# Minna_IO.net
KiCad netlist of a schematic drawn in Altium Designer
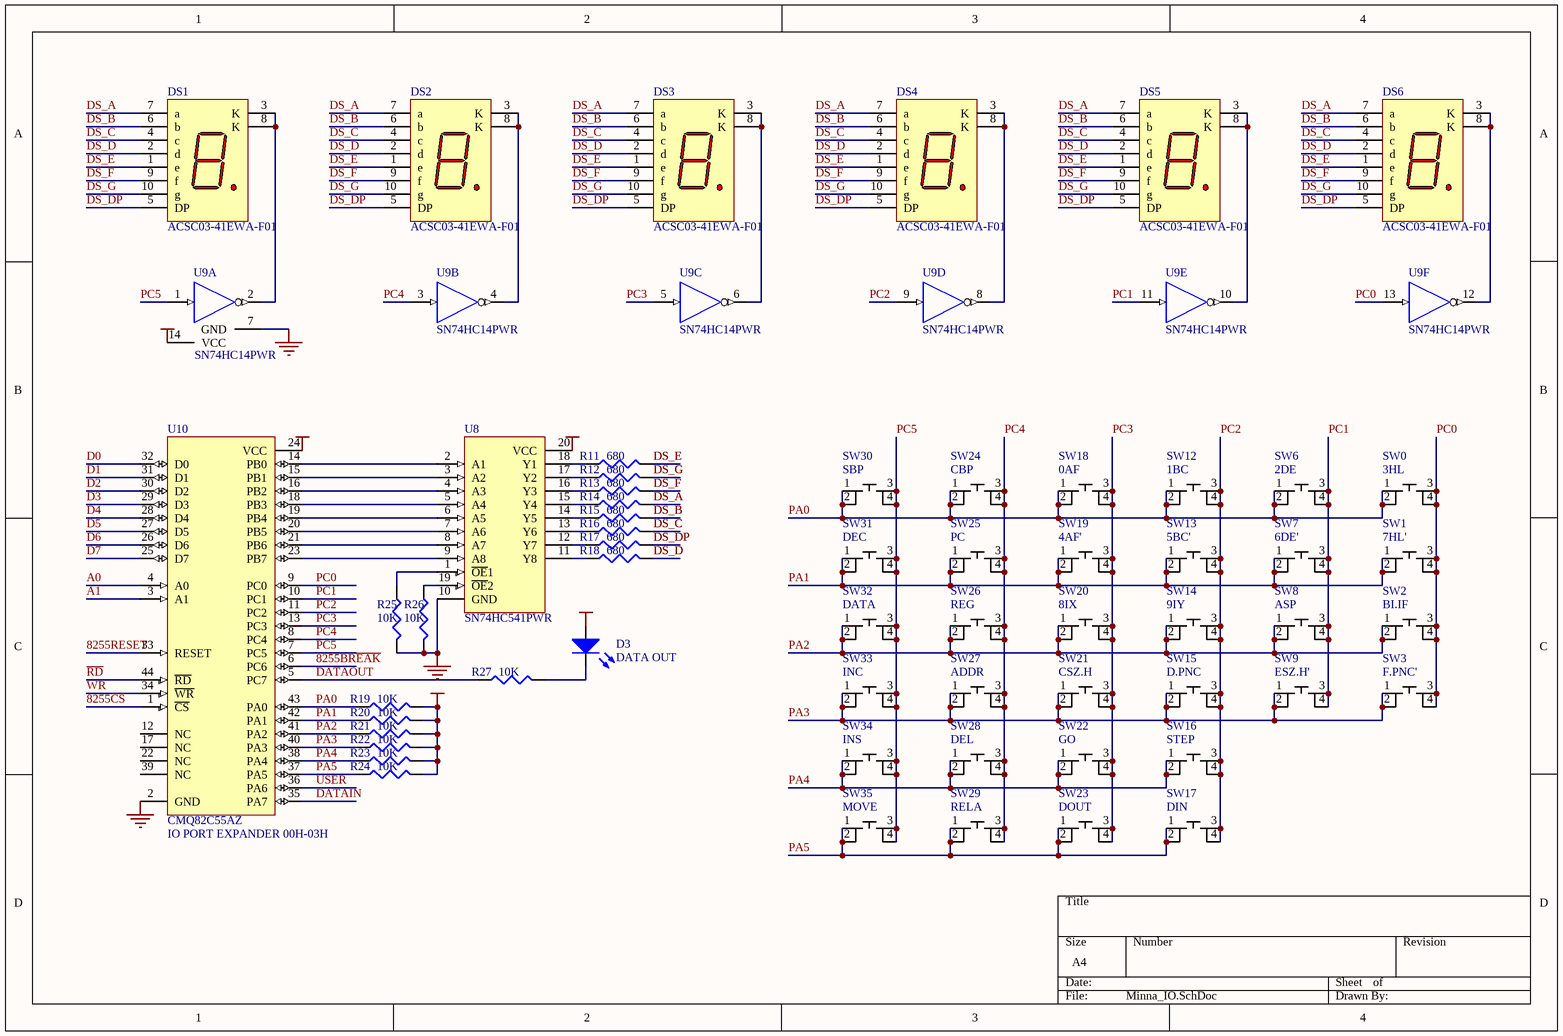
[diagram p0: Minna_IO.SchDoc]

(export (version "E")
  (design (tool "Eeschema 10.0.6"))
  (components
    (comp (ref "D3")
      (value "DATA OUT")
      (footprint "Minna Project:APG1608")
      (description "LED 1.6X0.8MM 571NM GRN CLR SMD")
      (libsource (lib "Minna Project") (part "APG1608CGKC/T"))
    )
    (comp (ref "DS1")
      (value "ACSC03-41EWA-F01")
      (footprint "Minna Project:ACSC03-41EWA-F01")
      (description "DISPLAY 0.3\" 627NM SGL RED SMD")
      (libsource (lib "Minna Project") (part "ACSC03-41EWA-F01"))
    )
    (comp (ref "DS2")
      (value "ACSC03-41EWA-F01")
      (footprint "Minna Project:ACSC03-41EWA-F01")
      (description "DISPLAY 0.3\" 627NM SGL RED SMD")
      (libsource (lib "Minna Project") (part "ACSC03-41EWA-F01"))
    )
    (comp (ref "DS3")
      (value "ACSC03-41EWA-F01")
      (footprint "Minna Project:ACSC03-41EWA-F01")
      (description "DISPLAY 0.3\" 627NM SGL RED SMD")
      (libsource (lib "Minna Project") (part "ACSC03-41EWA-F01"))
    )
    (comp (ref "DS4")
      (value "ACSC03-41EWA-F01")
      (footprint "Minna Project:ACSC03-41EWA-F01")
      (description "DISPLAY 0.3\" 627NM SGL RED SMD")
      (libsource (lib "Minna Project") (part "ACSC03-41EWA-F01"))
    )
    (comp (ref "DS5")
      (value "ACSC03-41EWA-F01")
      (footprint "Minna Project:ACSC03-41EWA-F01")
      (description "DISPLAY 0.3\" 627NM SGL RED SMD")
      (libsource (lib "Minna Project") (part "ACSC03-41EWA-F01"))
    )
    (comp (ref "DS6")
      (value "ACSC03-41EWA-F01")
      (footprint "Minna Project:ACSC03-41EWA-F01")
      (description "DISPLAY 0.3\" 627NM SGL RED SMD")
      (libsource (lib "Minna Project") (part "ACSC03-41EWA-F01"))
    )
    (comp (ref "R11")
      (value "680")
      (footprint "Minna Project:0603")
      (description "RES 680 OHM 1/10W 1% 0603 SMD")
      (libsource (lib "Minna Project") (part "MCR03EZPFX"))
    )
    (comp (ref "R12")
      (value "680")
      (footprint "Minna Project:0603")
      (description "RES 680 OHM 1/10W 1% 0603 SMD")
      (libsource (lib "Minna Project") (part "MCR03EZPFX"))
    )
    (comp (ref "R13")
      (value "680")
      (footprint "Minna Project:0603")
      (description "RES 680 OHM 1/10W 1% 0603 SMD")
      (libsource (lib "Minna Project") (part "MCR03EZPFX"))
    )
    (comp (ref "R14")
      (value "680")
      (footprint "Minna Project:0603")
      (description "RES 680 OHM 1/10W 1% 0603 SMD")
      (libsource (lib "Minna Project") (part "MCR03EZPFX"))
    )
    (comp (ref "R15")
      (value "680")
      (footprint "Minna Project:0603")
      (description "RES 680 OHM 1/10W 1% 0603 SMD")
      (libsource (lib "Minna Project") (part "MCR03EZPFX"))
    )
    (comp (ref "R16")
      (value "680")
      (footprint "Minna Project:0603")
      (description "RES 680 OHM 1/10W 1% 0603 SMD")
      (libsource (lib "Minna Project") (part "MCR03EZPFX"))
    )
    (comp (ref "R17")
      (value "680")
      (footprint "Minna Project:0603")
      (description "RES 680 OHM 1/10W 1% 0603 SMD")
      (libsource (lib "Minna Project") (part "MCR03EZPFX"))
    )
    (comp (ref "R18")
      (value "680")
      (footprint "Minna Project:0603")
      (description "RES 680 OHM 1/10W 1% 0603 SMD")
      (libsource (lib "Minna Project") (part "MCR03EZPFX"))
    )
    (comp (ref "R19")
      (value "10K")
      (footprint "Minna Project:0603")
      (description "RES 10.0K OHM 1/10W 1% 0603 SMD")
      (libsource (lib "Minna Project") (part "MCR03EZPFX"))
    )
    (comp (ref "R20")
      (value "10K")
      (footprint "Minna Project:0603")
      (description "RES 10.0K OHM 1/10W 1% 0603 SMD")
      (libsource (lib "Minna Project") (part "MCR03EZPFX"))
    )
    (comp (ref "R21")
      (value "10K")
      (footprint "Minna Project:0603")
      (description "RES 10.0K OHM 1/10W 1% 0603 SMD")
      (libsource (lib "Minna Project") (part "MCR03EZPFX"))
    )
    (comp (ref "R22")
      (value "10K")
      (footprint "Minna Project:0603")
      (description "RES 10.0K OHM 1/10W 1% 0603 SMD")
      (libsource (lib "Minna Project") (part "MCR03EZPFX"))
    )
    (comp (ref "R23")
      (value "10K")
      (footprint "Minna Project:0603")
      (description "RES 10.0K OHM 1/10W 1% 0603 SMD")
      (libsource (lib "Minna Project") (part "MCR03EZPFX"))
    )
    (comp (ref "R24")
      (value "10K")
      (footprint "Minna Project:0603")
      (description "RES 10.0K OHM 1/10W 1% 0603 SMD")
      (libsource (lib "Minna Project") (part "MCR03EZPFX"))
    )
    (comp (ref "R25")
      (value "10K")
      (footprint "Minna Project:0603")
      (description "RES 10.0K OHM 1/10W 1% 0603 SMD")
      (libsource (lib "Minna Project") (part "MCR03EZPFX"))
    )
    (comp (ref "R26")
      (value "10K")
      (footprint "Minna Project:0603")
      (description "RES 10.0K OHM 1/10W 1% 0603 SMD")
      (libsource (lib "Minna Project") (part "MCR03EZPFX"))
    )
    (comp (ref "R27")
      (value "10K")
      (footprint "Minna Project:0603")
      (description "RES 10.0K OHM 1/10W 1% 0603 SMD")
      (libsource (lib "Minna Project") (part "MCR03EZPFX"))
    )
    (comp (ref "SW0")
      (value "3HL")
      (footprint "Minna Project:PTS645SM43SMTR LFS")
      (description "SWITCH TACT 6MM 160GF H=4.3MM")
      (libsource (lib "Minna Project") (part "PTS645SM43SMTR LFS"))
    )
    (comp (ref "SW1")
      (value "7HL'")
      (footprint "Minna Project:PTS645SM43SMTR LFS")
      (description "SWITCH TACT 6MM 160GF H=4.3MM")
      (libsource (lib "Minna Project") (part "PTS645SM43SMTR LFS"))
    )
    (comp (ref "SW2")
      (value "BI.IF")
      (footprint "Minna Project:PTS645SM43SMTR LFS")
      (description "SWITCH TACT 6MM 160GF H=4.3MM")
      (libsource (lib "Minna Project") (part "PTS645SM43SMTR LFS"))
    )
    (comp (ref "SW3")
      (value "F.PNC'")
      (footprint "Minna Project:PTS645SM43SMTR LFS")
      (description "SWITCH TACT 6MM 160GF H=4.3MM")
      (libsource (lib "Minna Project") (part "PTS645SM43SMTR LFS"))
    )
    (comp (ref "SW6")
      (value "2DE")
      (footprint "Minna Project:PTS645SM43SMTR LFS")
      (description "SWITCH TACT 6MM 160GF H=4.3MM")
      (libsource (lib "Minna Project") (part "PTS645SM43SMTR LFS"))
    )
    (comp (ref "SW7")
      (value "6DE'")
      (footprint "Minna Project:PTS645SM43SMTR LFS")
      (description "SWITCH TACT 6MM 160GF H=4.3MM")
      (libsource (lib "Minna Project") (part "PTS645SM43SMTR LFS"))
    )
    (comp (ref "SW8")
      (value "ASP")
      (footprint "Minna Project:PTS645SM43SMTR LFS")
      (description "SWITCH TACT 6MM 160GF H=4.3MM")
      (libsource (lib "Minna Project") (part "PTS645SM43SMTR LFS"))
    )
    (comp (ref "SW9")
      (value "ESZ.H'")
      (footprint "Minna Project:PTS645SM43SMTR LFS")
      (description "SWITCH TACT 6MM 160GF H=4.3MM")
      (libsource (lib "Minna Project") (part "PTS645SM43SMTR LFS"))
    )
    (comp (ref "SW12")
      (value "1BC")
      (footprint "Minna Project:PTS645SM43SMTR LFS")
      (description "SWITCH TACT 6MM 160GF H=4.3MM")
      (libsource (lib "Minna Project") (part "PTS645SM43SMTR LFS"))
    )
    (comp (ref "SW13")
      (value "5BC'")
      (footprint "Minna Project:PTS645SM43SMTR LFS")
      (description "SWITCH TACT 6MM 160GF H=4.3MM")
      (libsource (lib "Minna Project") (part "PTS645SM43SMTR LFS"))
    )
    (comp (ref "SW14")
      (value "9IY")
      (footprint "Minna Project:PTS645SM43SMTR LFS")
      (description "SWITCH TACT 6MM 160GF H=4.3MM")
      (libsource (lib "Minna Project") (part "PTS645SM43SMTR LFS"))
    )
    (comp (ref "SW15")
      (value "D.PNC")
      (footprint "Minna Project:PTS645SM43SMTR LFS")
      (description "SWITCH TACT 6MM 160GF H=4.3MM")
      (libsource (lib "Minna Project") (part "PTS645SM43SMTR LFS"))
    )
    (comp (ref "SW16")
      (value "STEP")
      (footprint "Minna Project:PTS645SM43SMTR LFS")
      (description "SWITCH TACT 6MM 160GF H=4.3MM")
      (libsource (lib "Minna Project") (part "PTS645SM43SMTR LFS"))
    )
    (comp (ref "SW17")
      (value "DIN")
      (footprint "Minna Project:PTS645SM43SMTR LFS")
      (description "SWITCH TACT 6MM 160GF H=4.3MM")
      (libsource (lib "Minna Project") (part "PTS645SM43SMTR LFS"))
    )
    (comp (ref "SW18")
      (value "0AF")
      (footprint "Minna Project:PTS645SM43SMTR LFS")
      (description "SWITCH TACT 6MM 160GF H=4.3MM")
      (libsource (lib "Minna Project") (part "PTS645SM43SMTR LFS"))
    )
    (comp (ref "SW19")
      (value "4AF'")
      (footprint "Minna Project:PTS645SM43SMTR LFS")
      (description "SWITCH TACT 6MM 160GF H=4.3MM")
      (libsource (lib "Minna Project") (part "PTS645SM43SMTR LFS"))
    )
    (comp (ref "SW20")
      (value "8IX")
      (footprint "Minna Project:PTS645SM43SMTR LFS")
      (description "SWITCH TACT 6MM 160GF H=4.3MM")
      (libsource (lib "Minna Project") (part "PTS645SM43SMTR LFS"))
    )
    (comp (ref "SW21")
      (value "CSZ.H")
      (footprint "Minna Project:PTS645SM43SMTR LFS")
      (description "SWITCH TACT 6MM 160GF H=4.3MM")
      (libsource (lib "Minna Project") (part "PTS645SM43SMTR LFS"))
    )
    (comp (ref "SW22")
      (value "GO")
      (footprint "Minna Project:PTS645SM43SMTR LFS")
      (description "SWITCH TACT 6MM 160GF H=4.3MM")
      (libsource (lib "Minna Project") (part "PTS645SM43SMTR LFS"))
    )
    (comp (ref "SW23")
      (value "DOUT")
      (footprint "Minna Project:PTS645SM43SMTR LFS")
      (description "SWITCH TACT 6MM 160GF H=4.3MM")
      (libsource (lib "Minna Project") (part "PTS645SM43SMTR LFS"))
    )
    (comp (ref "SW24")
      (value "CBP")
      (footprint "Minna Project:PTS645SM43SMTR LFS")
      (description "SWITCH TACT 6MM 160GF H=4.3MM")
      (libsource (lib "Minna Project") (part "PTS645SM43SMTR LFS"))
    )
    (comp (ref "SW25")
      (value "PC")
      (footprint "Minna Project:PTS645SM43SMTR LFS")
      (description "SWITCH TACT 6MM 160GF H=4.3MM")
      (libsource (lib "Minna Project") (part "PTS645SM43SMTR LFS"))
    )
    (comp (ref "SW26")
      (value "REG")
      (footprint "Minna Project:PTS645SM43SMTR LFS")
      (description "SWITCH TACT 6MM 160GF H=4.3MM")
      (libsource (lib "Minna Project") (part "PTS645SM43SMTR LFS"))
    )
    (comp (ref "SW27")
      (value "ADDR")
      (footprint "Minna Project:PTS645SM43SMTR LFS")
      (description "SWITCH TACT 6MM 160GF H=4.3MM")
      (libsource (lib "Minna Project") (part "PTS645SM43SMTR LFS"))
    )
    (comp (ref "SW28")
      (value "DEL")
      (footprint "Minna Project:PTS645SM43SMTR LFS")
      (description "SWITCH TACT 6MM 160GF H=4.3MM")
      (libsource (lib "Minna Project") (part "PTS645SM43SMTR LFS"))
    )
    (comp (ref "SW29")
      (value "RELA")
      (footprint "Minna Project:PTS645SM43SMTR LFS")
      (description "SWITCH TACT 6MM 160GF H=4.3MM")
      (libsource (lib "Minna Project") (part "PTS645SM43SMTR LFS"))
    )
    (comp (ref "SW30")
      (value "SBP")
      (footprint "Minna Project:PTS645SM43SMTR LFS")
      (description "SWITCH TACT 6MM 160GF H=4.3MM")
      (libsource (lib "Minna Project") (part "PTS645SM43SMTR LFS"))
    )
    (comp (ref "SW31")
      (value "DEC")
      (footprint "Minna Project:PTS645SM43SMTR LFS")
      (description "SWITCH TACT 6MM 160GF H=4.3MM")
      (libsource (lib "Minna Project") (part "PTS645SM43SMTR LFS"))
    )
    (comp (ref "SW32")
      (value "DATA")
      (footprint "Minna Project:PTS645SM43SMTR LFS")
      (description "SWITCH TACT 6MM 160GF H=4.3MM")
      (libsource (lib "Minna Project") (part "PTS645SM43SMTR LFS"))
    )
    (comp (ref "SW33")
      (value "INC")
      (footprint "Minna Project:PTS645SM43SMTR LFS")
      (description "SWITCH TACT 6MM 160GF H=4.3MM")
      (libsource (lib "Minna Project") (part "PTS645SM43SMTR LFS"))
    )
    (comp (ref "SW34")
      (value "INS")
      (footprint "Minna Project:PTS645SM43SMTR LFS")
      (description "SWITCH TACT 6MM 160GF H=4.3MM")
      (libsource (lib "Minna Project") (part "PTS645SM43SMTR LFS"))
    )
    (comp (ref "SW35")
      (value "MOVE")
      (footprint "Minna Project:PTS645SM43SMTR LFS")
      (description "SWITCH TACT 6MM 160GF H=4.3MM")
      (libsource (lib "Minna Project") (part "PTS645SM43SMTR LFS"))
    )
    (comp (ref "U8")
      (value "SN74HC541PWR")
      (footprint "Minna Project:PW020")
      (description "IC BUFF/DVR TRI-ST 8BIT 20TSSOP")
      (libsource (lib "Minna Project") (part "SN74HC541PWR"))
    )
    (comp (ref "U9")
      (value "SN74HC14PWR")
      (footprint "Minna Project:PW014")
      (description "IC HEX SCHMITT-TRIG INV 14-TSSOP")
      (libsource (lib "") (part "SN74HC14PWR_1"))
    )
    (comp (ref "U10")
      (value "CMQ82C55AZ")
      (footprint "Minna Project:MQFP-44")
      (description "IC I/O EXPANDER 24B 44MQFP")
      (fields (field (name "NOTES") "IO PORT EXPANDER 00H-03H"))
      (libsource (lib "Minna Project") (part "CMQ82C55AZ"))
    )
  )
  (nets
    (net (code "1") (name "/8255RESET") (class "Default")
      (node (ref "U10") (pin "33") (pinfunction "RESET_33") (pintype "input"))
    )
    (net (code "2") (name "/8255~{BREAK}") (class "Default")
      (node (ref "U10") (pin "6") (pinfunction "PC6_6") (pintype "bidirectional"))
    )
    (net (code "3") (name "/8255~{CS}") (class "Default")
      (node (ref "U10") (pin "1") (pinfunction "~{CS}_1") (pintype "input"))
    )
    (net (code "4") (name "/A0") (class "Default")
      (node (ref "U10") (pin "4") (pinfunction "A0_4") (pintype "input"))
    )
    (net (code "5") (name "/A1") (class "Default")
      (node (ref "U10") (pin "3") (pinfunction "A1_3") (pintype "input"))
    )
    (net (code "6") (name "/D0") (class "Default")
      (node (ref "U10") (pin "32") (pinfunction "D0_32") (pintype "bidirectional"))
    )
    (net (code "7") (name "/D1") (class "Default")
      (node (ref "U10") (pin "31") (pinfunction "D1_31") (pintype "bidirectional"))
    )
    (net (code "8") (name "/D2") (class "Default")
      (node (ref "U10") (pin "30") (pinfunction "D2_30") (pintype "bidirectional"))
    )
    (net (code "9") (name "/D3") (class "Default")
      (node (ref "U10") (pin "29") (pinfunction "D3_29") (pintype "bidirectional"))
    )
    (net (code "10") (name "/D4") (class "Default")
      (node (ref "U10") (pin "28") (pinfunction "D4_28") (pintype "bidirectional"))
    )
    (net (code "11") (name "/D5") (class "Default")
      (node (ref "U10") (pin "27") (pinfunction "D5_27") (pintype "bidirectional"))
    )
    (net (code "12") (name "/D6") (class "Default")
      (node (ref "U10") (pin "26") (pinfunction "D6_26") (pintype "bidirectional"))
    )
    (net (code "13") (name "/D7") (class "Default")
      (node (ref "U10") (pin "25") (pinfunction "D7_25") (pintype "bidirectional"))
    )
    (net (code "14") (name "/DATAIN") (class "Default")
      (node (ref "U10") (pin "35") (pinfunction "PA7_35") (pintype "bidirectional"))
    )
    (net (code "15") (name "/DATAOUT") (class "Default")
      (node (ref "R27") (pin "1") (pinfunction "1_1") (pintype "passive"))
      (node (ref "U10") (pin "5") (pinfunction "PC7_5") (pintype "bidirectional"))
    )
    (net (code "16") (name "/DS_A") (class "Default")
      (node (ref "DS1") (pin "7") (pinfunction "a_7") (pintype "passive"))
      (node (ref "DS2") (pin "7") (pinfunction "a_7") (pintype "passive"))
      (node (ref "DS3") (pin "7") (pinfunction "a_7") (pintype "passive"))
      (node (ref "DS4") (pin "7") (pinfunction "a_7") (pintype "passive"))
      (node (ref "DS5") (pin "7") (pinfunction "a_7") (pintype "passive"))
      (node (ref "DS6") (pin "7") (pinfunction "a_7") (pintype "passive"))
      (node (ref "R14") (pin "2") (pinfunction "2_2") (pintype "passive"))
    )
    (net (code "17") (name "/DS_B") (class "Default")
      (node (ref "DS1") (pin "6") (pinfunction "b_6") (pintype "passive"))
      (node (ref "DS2") (pin "6") (pinfunction "b_6") (pintype "passive"))
      (node (ref "DS3") (pin "6") (pinfunction "b_6") (pintype "passive"))
      (node (ref "DS4") (pin "6") (pinfunction "b_6") (pintype "passive"))
      (node (ref "DS5") (pin "6") (pinfunction "b_6") (pintype "passive"))
      (node (ref "DS6") (pin "6") (pinfunction "b_6") (pintype "passive"))
      (node (ref "R15") (pin "2") (pinfunction "2_2") (pintype "passive"))
    )
    (net (code "18") (name "/DS_C") (class "Default")
      (node (ref "DS1") (pin "4") (pinfunction "c_4") (pintype "passive"))
      (node (ref "DS2") (pin "4") (pinfunction "c_4") (pintype "passive"))
      (node (ref "DS3") (pin "4") (pinfunction "c_4") (pintype "passive"))
      (node (ref "DS4") (pin "4") (pinfunction "c_4") (pintype "passive"))
      (node (ref "DS5") (pin "4") (pinfunction "c_4") (pintype "passive"))
      (node (ref "DS6") (pin "4") (pinfunction "c_4") (pintype "passive"))
      (node (ref "R16") (pin "2") (pinfunction "2_2") (pintype "passive"))
    )
    (net (code "19") (name "/DS_D") (class "Default")
      (node (ref "DS1") (pin "2") (pinfunction "d_2") (pintype "passive"))
      (node (ref "DS2") (pin "2") (pinfunction "d_2") (pintype "passive"))
      (node (ref "DS3") (pin "2") (pinfunction "d_2") (pintype "passive"))
      (node (ref "DS4") (pin "2") (pinfunction "d_2") (pintype "passive"))
      (node (ref "DS5") (pin "2") (pinfunction "d_2") (pintype "passive"))
      (node (ref "DS6") (pin "2") (pinfunction "d_2") (pintype "passive"))
      (node (ref "R18") (pin "2") (pinfunction "2_2") (pintype "passive"))
    )
    (net (code "20") (name "/DS_DP") (class "Default")
      (node (ref "DS1") (pin "5") (pinfunction "DP_5") (pintype "passive"))
      (node (ref "DS2") (pin "5") (pinfunction "DP_5") (pintype "passive"))
      (node (ref "DS3") (pin "5") (pinfunction "DP_5") (pintype "passive"))
      (node (ref "DS4") (pin "5") (pinfunction "DP_5") (pintype "passive"))
      (node (ref "DS5") (pin "5") (pinfunction "DP_5") (pintype "passive"))
      (node (ref "DS6") (pin "5") (pinfunction "DP_5") (pintype "passive"))
      (node (ref "R17") (pin "2") (pinfunction "2_2") (pintype "passive"))
    )
    (net (code "21") (name "/DS_E") (class "Default")
      (node (ref "DS1") (pin "1") (pinfunction "e_1") (pintype "passive"))
      (node (ref "DS2") (pin "1") (pinfunction "e_1") (pintype "passive"))
      (node (ref "DS3") (pin "1") (pinfunction "e_1") (pintype "passive"))
      (node (ref "DS4") (pin "1") (pinfunction "e_1") (pintype "passive"))
      (node (ref "DS5") (pin "1") (pinfunction "e_1") (pintype "passive"))
      (node (ref "DS6") (pin "1") (pinfunction "e_1") (pintype "passive"))
      (node (ref "R11") (pin "2") (pinfunction "2_2") (pintype "passive"))
    )
    (net (code "22") (name "/DS_F") (class "Default")
      (node (ref "DS1") (pin "9") (pinfunction "f_9") (pintype "passive"))
      (node (ref "DS2") (pin "9") (pinfunction "f_9") (pintype "passive"))
      (node (ref "DS3") (pin "9") (pinfunction "f_9") (pintype "passive"))
      (node (ref "DS4") (pin "9") (pinfunction "f_9") (pintype "passive"))
      (node (ref "DS5") (pin "9") (pinfunction "f_9") (pintype "passive"))
      (node (ref "DS6") (pin "9") (pinfunction "f_9") (pintype "passive"))
      (node (ref "R13") (pin "2") (pinfunction "2_2") (pintype "passive"))
    )
    (net (code "23") (name "/DS_G") (class "Default")
      (node (ref "DS1") (pin "10") (pinfunction "g_10") (pintype "passive"))
      (node (ref "DS2") (pin "10") (pinfunction "g_10") (pintype "passive"))
      (node (ref "DS3") (pin "10") (pinfunction "g_10") (pintype "passive"))
      (node (ref "DS4") (pin "10") (pinfunction "g_10") (pintype "passive"))
      (node (ref "DS5") (pin "10") (pinfunction "g_10") (pintype "passive"))
      (node (ref "DS6") (pin "10") (pinfunction "g_10") (pintype "passive"))
      (node (ref "R12") (pin "2") (pinfunction "2_2") (pintype "passive"))
    )
    (net (code "24") (name "/PA0") (class "Default")
      (node (ref "R19") (pin "1") (pinfunction "1_1") (pintype "passive"))
      (node (ref "SW0") (pin "1") (pinfunction "1_1") (pintype "passive"))
      (node (ref "SW0") (pin "2") (pinfunction "2_2") (pintype "passive"))
      (node (ref "SW12") (pin "1") (pinfunction "1_1") (pintype "passive"))
      (node (ref "SW12") (pin "2") (pinfunction "2_2") (pintype "passive"))
      (node (ref "SW18") (pin "1") (pinfunction "1_1") (pintype "passive"))
      (node (ref "SW18") (pin "2") (pinfunction "2_2") (pintype "passive"))
      (node (ref "SW24") (pin "1") (pinfunction "1_1") (pintype "passive"))
      (node (ref "SW24") (pin "2") (pinfunction "2_2") (pintype "passive"))
      (node (ref "SW30") (pin "1") (pinfunction "1_1") (pintype "passive"))
      (node (ref "SW30") (pin "2") (pinfunction "2_2") (pintype "passive"))
      (node (ref "SW6") (pin "1") (pinfunction "1_1") (pintype "passive"))
      (node (ref "SW6") (pin "2") (pinfunction "2_2") (pintype "passive"))
      (node (ref "U10") (pin "43") (pinfunction "PA0_43") (pintype "bidirectional"))
    )
    (net (code "25") (name "/PA1") (class "Default")
      (node (ref "R20") (pin "1") (pinfunction "1_1") (pintype "passive"))
      (node (ref "SW1") (pin "1") (pinfunction "1_1") (pintype "passive"))
      (node (ref "SW1") (pin "2") (pinfunction "2_2") (pintype "passive"))
      (node (ref "SW13") (pin "1") (pinfunction "1_1") (pintype "passive"))
      (node (ref "SW13") (pin "2") (pinfunction "2_2") (pintype "passive"))
      (node (ref "SW19") (pin "1") (pinfunction "1_1") (pintype "passive"))
      (node (ref "SW19") (pin "2") (pinfunction "2_2") (pintype "passive"))
      (node (ref "SW25") (pin "1") (pinfunction "1_1") (pintype "passive"))
      (node (ref "SW25") (pin "2") (pinfunction "2_2") (pintype "passive"))
      (node (ref "SW31") (pin "1") (pinfunction "1_1") (pintype "passive"))
      (node (ref "SW31") (pin "2") (pinfunction "2_2") (pintype "passive"))
      (node (ref "SW7") (pin "1") (pinfunction "1_1") (pintype "passive"))
      (node (ref "SW7") (pin "2") (pinfunction "2_2") (pintype "passive"))
      (node (ref "U10") (pin "42") (pinfunction "PA1_42") (pintype "bidirectional"))
    )
    (net (code "26") (name "/PA2") (class "Default")
      (node (ref "R21") (pin "1") (pinfunction "1_1") (pintype "passive"))
      (node (ref "SW14") (pin "1") (pinfunction "1_1") (pintype "passive"))
      (node (ref "SW14") (pin "2") (pinfunction "2_2") (pintype "passive"))
      (node (ref "SW2") (pin "1") (pinfunction "1_1") (pintype "passive"))
      (node (ref "SW2") (pin "2") (pinfunction "2_2") (pintype "passive"))
      (node (ref "SW20") (pin "1") (pinfunction "1_1") (pintype "passive"))
      (node (ref "SW20") (pin "2") (pinfunction "2_2") (pintype "passive"))
      (node (ref "SW26") (pin "1") (pinfunction "1_1") (pintype "passive"))
      (node (ref "SW26") (pin "2") (pinfunction "2_2") (pintype "passive"))
      (node (ref "SW32") (pin "1") (pinfunction "1_1") (pintype "passive"))
      (node (ref "SW32") (pin "2") (pinfunction "2_2") (pintype "passive"))
      (node (ref "SW8") (pin "1") (pinfunction "1_1") (pintype "passive"))
      (node (ref "SW8") (pin "2") (pinfunction "2_2") (pintype "passive"))
      (node (ref "U10") (pin "41") (pinfunction "PA2_41") (pintype "bidirectional"))
    )
    (net (code "27") (name "/PA3") (class "Default")
      (node (ref "R22") (pin "1") (pinfunction "1_1") (pintype "passive"))
      (node (ref "SW15") (pin "1") (pinfunction "1_1") (pintype "passive"))
      (node (ref "SW15") (pin "2") (pinfunction "2_2") (pintype "passive"))
      (node (ref "SW21") (pin "1") (pinfunction "1_1") (pintype "passive"))
      (node (ref "SW21") (pin "2") (pinfunction "2_2") (pintype "passive"))
      (node (ref "SW27") (pin "1") (pinfunction "1_1") (pintype "passive"))
      (node (ref "SW27") (pin "2") (pinfunction "2_2") (pintype "passive"))
      (node (ref "SW3") (pin "1") (pinfunction "1_1") (pintype "passive"))
      (node (ref "SW3") (pin "2") (pinfunction "2_2") (pintype "passive"))
      (node (ref "SW33") (pin "1") (pinfunction "1_1") (pintype "passive"))
      (node (ref "SW33") (pin "2") (pinfunction "2_2") (pintype "passive"))
      (node (ref "SW9") (pin "1") (pinfunction "1_1") (pintype "passive"))
      (node (ref "SW9") (pin "2") (pinfunction "2_2") (pintype "passive"))
      (node (ref "U10") (pin "40") (pinfunction "PA3_40") (pintype "bidirectional"))
    )
    (net (code "28") (name "/PA4") (class "Default")
      (node (ref "R23") (pin "1") (pinfunction "1_1") (pintype "passive"))
      (node (ref "SW16") (pin "1") (pinfunction "1_1") (pintype "passive"))
      (node (ref "SW16") (pin "2") (pinfunction "2_2") (pintype "passive"))
      (node (ref "SW22") (pin "1") (pinfunction "1_1") (pintype "passive"))
      (node (ref "SW22") (pin "2") (pinfunction "2_2") (pintype "passive"))
      (node (ref "SW28") (pin "1") (pinfunction "1_1") (pintype "passive"))
      (node (ref "SW28") (pin "2") (pinfunction "2_2") (pintype "passive"))
      (node (ref "SW34") (pin "1") (pinfunction "1_1") (pintype "passive"))
      (node (ref "SW34") (pin "2") (pinfunction "2_2") (pintype "passive"))
      (node (ref "U10") (pin "38") (pinfunction "PA4_38") (pintype "bidirectional"))
    )
    (net (code "29") (name "/PA5") (class "Default")
      (node (ref "R24") (pin "1") (pinfunction "1_1") (pintype "passive"))
      (node (ref "SW17") (pin "1") (pinfunction "1_1") (pintype "passive"))
      (node (ref "SW17") (pin "2") (pinfunction "2_2") (pintype "passive"))
      (node (ref "SW23") (pin "1") (pinfunction "1_1") (pintype "passive"))
      (node (ref "SW23") (pin "2") (pinfunction "2_2") (pintype "passive"))
      (node (ref "SW29") (pin "1") (pinfunction "1_1") (pintype "passive"))
      (node (ref "SW29") (pin "2") (pinfunction "2_2") (pintype "passive"))
      (node (ref "SW35") (pin "1") (pinfunction "1_1") (pintype "passive"))
      (node (ref "SW35") (pin "2") (pinfunction "2_2") (pintype "passive"))
      (node (ref "U10") (pin "37") (pinfunction "PA5_37") (pintype "bidirectional"))
    )
    (net (code "30") (name "/PC0") (class "Default")
      (node (ref "SW0") (pin "3") (pinfunction "3_3") (pintype "passive"))
      (node (ref "SW0") (pin "4") (pinfunction "4_4") (pintype "passive"))
      (node (ref "SW1") (pin "3") (pinfunction "3_3") (pintype "passive"))
      (node (ref "SW1") (pin "4") (pinfunction "4_4") (pintype "passive"))
      (node (ref "SW2") (pin "3") (pinfunction "3_3") (pintype "passive"))
      (node (ref "SW2") (pin "4") (pinfunction "4_4") (pintype "passive"))
      (node (ref "SW3") (pin "3") (pinfunction "3_3") (pintype "passive"))
      (node (ref "SW3") (pin "4") (pinfunction "4_4") (pintype "passive"))
      (node (ref "U10") (pin "9") (pinfunction "PC0_9") (pintype "bidirectional"))
      (node (ref "U9") (pin "13") (pinfunction "A_13") (pintype "input"))
    )
    (net (code "31") (name "/PC1") (class "Default")
      (node (ref "SW6") (pin "3") (pinfunction "3_3") (pintype "passive"))
      (node (ref "SW6") (pin "4") (pinfunction "4_4") (pintype "passive"))
      (node (ref "SW7") (pin "3") (pinfunction "3_3") (pintype "passive"))
      (node (ref "SW7") (pin "4") (pinfunction "4_4") (pintype "passive"))
      (node (ref "SW8") (pin "3") (pinfunction "3_3") (pintype "passive"))
      (node (ref "SW8") (pin "4") (pinfunction "4_4") (pintype "passive"))
      (node (ref "SW9") (pin "3") (pinfunction "3_3") (pintype "passive"))
      (node (ref "SW9") (pin "4") (pinfunction "4_4") (pintype "passive"))
      (node (ref "U10") (pin "10") (pinfunction "PC1_10") (pintype "bidirectional"))
      (node (ref "U9") (pin "11") (pinfunction "A_11") (pintype "input"))
    )
    (net (code "32") (name "/PC2") (class "Default")
      (node (ref "SW12") (pin "3") (pinfunction "3_3") (pintype "passive"))
      (node (ref "SW12") (pin "4") (pinfunction "4_4") (pintype "passive"))
      (node (ref "SW13") (pin "3") (pinfunction "3_3") (pintype "passive"))
      (node (ref "SW13") (pin "4") (pinfunction "4_4") (pintype "passive"))
      (node (ref "SW14") (pin "3") (pinfunction "3_3") (pintype "passive"))
      (node (ref "SW14") (pin "4") (pinfunction "4_4") (pintype "passive"))
      (node (ref "SW15") (pin "3") (pinfunction "3_3") (pintype "passive"))
      (node (ref "SW15") (pin "4") (pinfunction "4_4") (pintype "passive"))
      (node (ref "SW16") (pin "3") (pinfunction "3_3") (pintype "passive"))
      (node (ref "SW16") (pin "4") (pinfunction "4_4") (pintype "passive"))
      (node (ref "SW17") (pin "3") (pinfunction "3_3") (pintype "passive"))
      (node (ref "SW17") (pin "4") (pinfunction "4_4") (pintype "passive"))
      (node (ref "U10") (pin "11") (pinfunction "PC2_11") (pintype "bidirectional"))
      (node (ref "U9") (pin "9") (pinfunction "A_9") (pintype "input"))
    )
    (net (code "33") (name "/PC3") (class "Default")
      (node (ref "SW18") (pin "3") (pinfunction "3_3") (pintype "passive"))
      (node (ref "SW18") (pin "4") (pinfunction "4_4") (pintype "passive"))
      (node (ref "SW19") (pin "3") (pinfunction "3_3") (pintype "passive"))
      (node (ref "SW19") (pin "4") (pinfunction "4_4") (pintype "passive"))
      (node (ref "SW20") (pin "3") (pinfunction "3_3") (pintype "passive"))
      (node (ref "SW20") (pin "4") (pinfunction "4_4") (pintype "passive"))
      (node (ref "SW21") (pin "3") (pinfunction "3_3") (pintype "passive"))
      (node (ref "SW21") (pin "4") (pinfunction "4_4") (pintype "passive"))
      (node (ref "SW22") (pin "3") (pinfunction "3_3") (pintype "passive"))
      (node (ref "SW22") (pin "4") (pinfunction "4_4") (pintype "passive"))
      (node (ref "SW23") (pin "3") (pinfunction "3_3") (pintype "passive"))
      (node (ref "SW23") (pin "4") (pinfunction "4_4") (pintype "passive"))
      (node (ref "U10") (pin "13") (pinfunction "PC3_13") (pintype "bidirectional"))
      (node (ref "U9") (pin "5") (pinfunction "A_5") (pintype "input"))
    )
    (net (code "34") (name "/PC4") (class "Default")
      (node (ref "SW24") (pin "3") (pinfunction "3_3") (pintype "passive"))
      (node (ref "SW24") (pin "4") (pinfunction "4_4") (pintype "passive"))
      (node (ref "SW25") (pin "3") (pinfunction "3_3") (pintype "passive"))
      (node (ref "SW25") (pin "4") (pinfunction "4_4") (pintype "passive"))
      (node (ref "SW26") (pin "3") (pinfunction "3_3") (pintype "passive"))
      (node (ref "SW26") (pin "4") (pinfunction "4_4") (pintype "passive"))
      (node (ref "SW27") (pin "3") (pinfunction "3_3") (pintype "passive"))
      (node (ref "SW27") (pin "4") (pinfunction "4_4") (pintype "passive"))
      (node (ref "SW28") (pin "3") (pinfunction "3_3") (pintype "passive"))
      (node (ref "SW28") (pin "4") (pinfunction "4_4") (pintype "passive"))
      (node (ref "SW29") (pin "3") (pinfunction "3_3") (pintype "passive"))
      (node (ref "SW29") (pin "4") (pinfunction "4_4") (pintype "passive"))
      (node (ref "U10") (pin "8") (pinfunction "PC4_8") (pintype "bidirectional"))
      (node (ref "U9") (pin "3") (pinfunction "A_3") (pintype "input"))
    )
    (net (code "35") (name "/PC5") (class "Default")
      (node (ref "SW30") (pin "3") (pinfunction "3_3") (pintype "passive"))
      (node (ref "SW30") (pin "4") (pinfunction "4_4") (pintype "passive"))
      (node (ref "SW31") (pin "3") (pinfunction "3_3") (pintype "passive"))
      (node (ref "SW31") (pin "4") (pinfunction "4_4") (pintype "passive"))
      (node (ref "SW32") (pin "3") (pinfunction "3_3") (pintype "passive"))
      (node (ref "SW32") (pin "4") (pinfunction "4_4") (pintype "passive"))
      (node (ref "SW33") (pin "3") (pinfunction "3_3") (pintype "passive"))
      (node (ref "SW33") (pin "4") (pinfunction "4_4") (pintype "passive"))
      (node (ref "SW34") (pin "3") (pinfunction "3_3") (pintype "passive"))
      (node (ref "SW34") (pin "4") (pinfunction "4_4") (pintype "passive"))
      (node (ref "SW35") (pin "3") (pinfunction "3_3") (pintype "passive"))
      (node (ref "SW35") (pin "4") (pinfunction "4_4") (pintype "passive"))
      (node (ref "U10") (pin "7") (pinfunction "PC5_7") (pintype "bidirectional"))
      (node (ref "U9") (pin "1") (pinfunction "A_1") (pintype "input"))
    )
    (net (code "36") (name "/USER") (class "Default")
      (node (ref "U10") (pin "36") (pinfunction "PA6_36") (pintype "bidirectional"))
    )
    (net (code "37") (name "/~{RD}") (class "Default")
      (node (ref "U10") (pin "44") (pinfunction "~{RD}_44") (pintype "input"))
    )
    (net (code "38") (name "/~{WR}") (class "Default")
      (node (ref "U10") (pin "34") (pinfunction "~{WR}_34") (pintype "input"))
    )
    (net (code "39") (name "GND") (class "Default")
      (node (ref "R25") (pin "2") (pinfunction "2_2") (pintype "passive"))
      (node (ref "R26") (pin "2") (pinfunction "2_2") (pintype "passive"))
      (node (ref "U10") (pin "2") (pinfunction "GND_2") (pintype "power_in"))
      (node (ref "U8") (pin "10") (pinfunction "GND_10") (pintype "power_in"))
      (node (ref "U9") (pin "7") (pinfunction "GND_7") (pintype "power_in"))
    )
    (net (code "40") (name "Net-(D3-K)") (class "Default")
      (node (ref "D3") (pin "2") (pinfunction "K_2") (pintype "passive"))
      (node (ref "R27") (pin "2") (pinfunction "2_2") (pintype "passive"))
    )
    (net (code "41") (name "Net-(U8-Y1)") (class "Default")
      (node (ref "R11") (pin "1") (pinfunction "1_1") (pintype "passive"))
      (node (ref "U8") (pin "18") (pinfunction "Y1_18") (pintype "tri_state"))
    )
    (net (code "42") (name "Net-(U8-Y2)") (class "Default")
      (node (ref "R12") (pin "1") (pinfunction "1_1") (pintype "passive"))
      (node (ref "U8") (pin "17") (pinfunction "Y2_17") (pintype "tri_state"))
    )
    (net (code "43") (name "Net-(U8-Y3)") (class "Default")
      (node (ref "R13") (pin "1") (pinfunction "1_1") (pintype "passive"))
      (node (ref "U8") (pin "16") (pinfunction "Y3_16") (pintype "tri_state"))
    )
    (net (code "44") (name "Net-(U8-Y4)") (class "Default")
      (node (ref "R14") (pin "1") (pinfunction "1_1") (pintype "passive"))
      (node (ref "U8") (pin "15") (pinfunction "Y4_15") (pintype "tri_state"))
    )
    (net (code "45") (name "Net-(U8-Y5)") (class "Default")
      (node (ref "R15") (pin "1") (pinfunction "1_1") (pintype "passive"))
      (node (ref "U8") (pin "14") (pinfunction "Y5_14") (pintype "tri_state"))
    )
    (net (code "46") (name "Net-(U8-Y6)") (class "Default")
      (node (ref "R16") (pin "1") (pinfunction "1_1") (pintype "passive"))
      (node (ref "U8") (pin "13") (pinfunction "Y6_13") (pintype "tri_state"))
    )
    (net (code "47") (name "Net-(U8-Y7)") (class "Default")
      (node (ref "R17") (pin "1") (pinfunction "1_1") (pintype "passive"))
      (node (ref "U8") (pin "12") (pinfunction "Y7_12") (pintype "tri_state"))
    )
    (net (code "48") (name "Net-(U8-Y8)") (class "Default")
      (node (ref "R18") (pin "1") (pinfunction "1_1") (pintype "passive"))
      (node (ref "U8") (pin "11") (pinfunction "Y8_11") (pintype "tri_state"))
    )
    (net (code "49") (name "Net-(U8-~{OE}1)") (class "Default")
      (node (ref "R25") (pin "1") (pinfunction "1_1") (pintype "passive"))
      (node (ref "U8") (pin "1") (pinfunction "~{OE}1_1") (pintype "input"))
    )
    (net (code "50") (name "Net-(U8-~{OE}2)") (class "Default")
      (node (ref "R26") (pin "1") (pinfunction "1_1") (pintype "passive"))
      (node (ref "U8") (pin "19") (pinfunction "~{OE}2_19") (pintype "input"))
    )
    (net (code "51") (name "Net-(U9A-Y)") (class "Default")
      (node (ref "DS1") (pin "3") (pinfunction "K_3") (pintype "passive"))
      (node (ref "DS1") (pin "8") (pinfunction "K_8") (pintype "passive"))
      (node (ref "U9") (pin "2") (pinfunction "Y_2") (pintype "output"))
    )
    (net (code "52") (name "Net-(U9B-Y)") (class "Default")
      (node (ref "DS2") (pin "3") (pinfunction "K_3") (pintype "passive"))
      (node (ref "DS2") (pin "8") (pinfunction "K_8") (pintype "passive"))
      (node (ref "U9") (pin "4") (pinfunction "Y_4") (pintype "output"))
    )
    (net (code "53") (name "Net-(U9C-Y)") (class "Default")
      (node (ref "DS3") (pin "3") (pinfunction "K_3") (pintype "passive"))
      (node (ref "DS3") (pin "8") (pinfunction "K_8") (pintype "passive"))
      (node (ref "U9") (pin "6") (pinfunction "Y_6") (pintype "output"))
    )
    (net (code "54") (name "Net-(U9D-Y)") (class "Default")
      (node (ref "DS4") (pin "3") (pinfunction "K_3") (pintype "passive"))
      (node (ref "DS4") (pin "8") (pinfunction "K_8") (pintype "passive"))
      (node (ref "U9") (pin "8") (pinfunction "Y_8") (pintype "output"))
    )
    (net (code "55") (name "Net-(U9E-Y)") (class "Default")
      (node (ref "DS5") (pin "3") (pinfunction "K_3") (pintype "passive"))
      (node (ref "DS5") (pin "8") (pinfunction "K_8") (pintype "passive"))
      (node (ref "U9") (pin "10") (pinfunction "Y_10") (pintype "output"))
    )
    (net (code "56") (name "Net-(U9F-Y)") (class "Default")
      (node (ref "DS6") (pin "3") (pinfunction "K_3") (pintype "passive"))
      (node (ref "DS6") (pin "8") (pinfunction "K_8") (pintype "passive"))
      (node (ref "U9") (pin "12") (pinfunction "Y_12") (pintype "output"))
    )
    (net (code "57") (name "Net-(U10-PB0)") (class "Default")
      (node (ref "U10") (pin "14") (pinfunction "PB0_14") (pintype "bidirectional"))
      (node (ref "U8") (pin "2") (pinfunction "A1_2") (pintype "input"))
    )
    (net (code "58") (name "Net-(U10-PB1)") (class "Default")
      (node (ref "U10") (pin "15") (pinfunction "PB1_15") (pintype "bidirectional"))
      (node (ref "U8") (pin "3") (pinfunction "A2_3") (pintype "input"))
    )
    (net (code "59") (name "Net-(U10-PB2)") (class "Default")
      (node (ref "U10") (pin "16") (pinfunction "PB2_16") (pintype "bidirectional"))
      (node (ref "U8") (pin "4") (pinfunction "A3_4") (pintype "input"))
    )
    (net (code "60") (name "Net-(U10-PB3)") (class "Default")
      (node (ref "U10") (pin "18") (pinfunction "PB3_18") (pintype "bidirectional"))
      (node (ref "U8") (pin "5") (pinfunction "A4_5") (pintype "input"))
    )
    (net (code "61") (name "Net-(U10-PB4)") (class "Default")
      (node (ref "U10") (pin "19") (pinfunction "PB4_19") (pintype "bidirectional"))
      (node (ref "U8") (pin "6") (pinfunction "A5_6") (pintype "input"))
    )
    (net (code "62") (name "Net-(U10-PB5)") (class "Default")
      (node (ref "U10") (pin "20") (pinfunction "PB5_20") (pintype "bidirectional"))
      (node (ref "U8") (pin "7") (pinfunction "A6_7") (pintype "input"))
    )
    (net (code "63") (name "Net-(U10-PB6)") (class "Default")
      (node (ref "U10") (pin "21") (pinfunction "PB6_21") (pintype "bidirectional"))
      (node (ref "U8") (pin "8") (pinfunction "A7_8") (pintype "input"))
    )
    (net (code "64") (name "Net-(U10-PB7)") (class "Default")
      (node (ref "U10") (pin "23") (pinfunction "PB7_23") (pintype "bidirectional"))
      (node (ref "U8") (pin "9") (pinfunction "A8_9") (pintype "input"))
    )
    (net (code "65") (name "VCC") (class "Default")
      (node (ref "D3") (pin "1") (pinfunction "A_1") (pintype "passive"))
      (node (ref "R19") (pin "2") (pinfunction "2_2") (pintype "passive"))
      (node (ref "R20") (pin "2") (pinfunction "2_2") (pintype "passive"))
      (node (ref "R21") (pin "2") (pinfunction "2_2") (pintype "passive"))
      (node (ref "R22") (pin "2") (pinfunction "2_2") (pintype "passive"))
      (node (ref "R23") (pin "2") (pinfunction "2_2") (pintype "passive"))
      (node (ref "R24") (pin "2") (pinfunction "2_2") (pintype "passive"))
      (node (ref "U10") (pin "24") (pinfunction "VCC_24") (pintype "power_in"))
      (node (ref "U8") (pin "20") (pinfunction "VCC_20") (pintype "power_in"))
      (node (ref "U9") (pin "14") (pinfunction "VCC_14") (pintype "power_in"))
    )
    (net (code "66") (name "unconnected-(U10-NC-Pad12)") (class "Default")
      (node (ref "U10") (pin "12") (pinfunction "NC_12") (pintype "passive"))
    )
    (net (code "67") (name "unconnected-(U10-NC-Pad17)") (class "Default")
      (node (ref "U10") (pin "17") (pinfunction "NC_17") (pintype "passive"))
    )
    (net (code "68") (name "unconnected-(U10-NC-Pad22)") (class "Default")
      (node (ref "U10") (pin "22") (pinfunction "NC_22") (pintype "passive"))
    )
    (net (code "69") (name "unconnected-(U10-NC-Pad39)") (class "Default")
      (node (ref "U10") (pin "39") (pinfunction "NC_39") (pintype "passive"))
    )
  )
)
